# SCH_Controlador-de-Voo_2026-04-27.net
KiCad netlist of a schematic drawn in EasyEDA
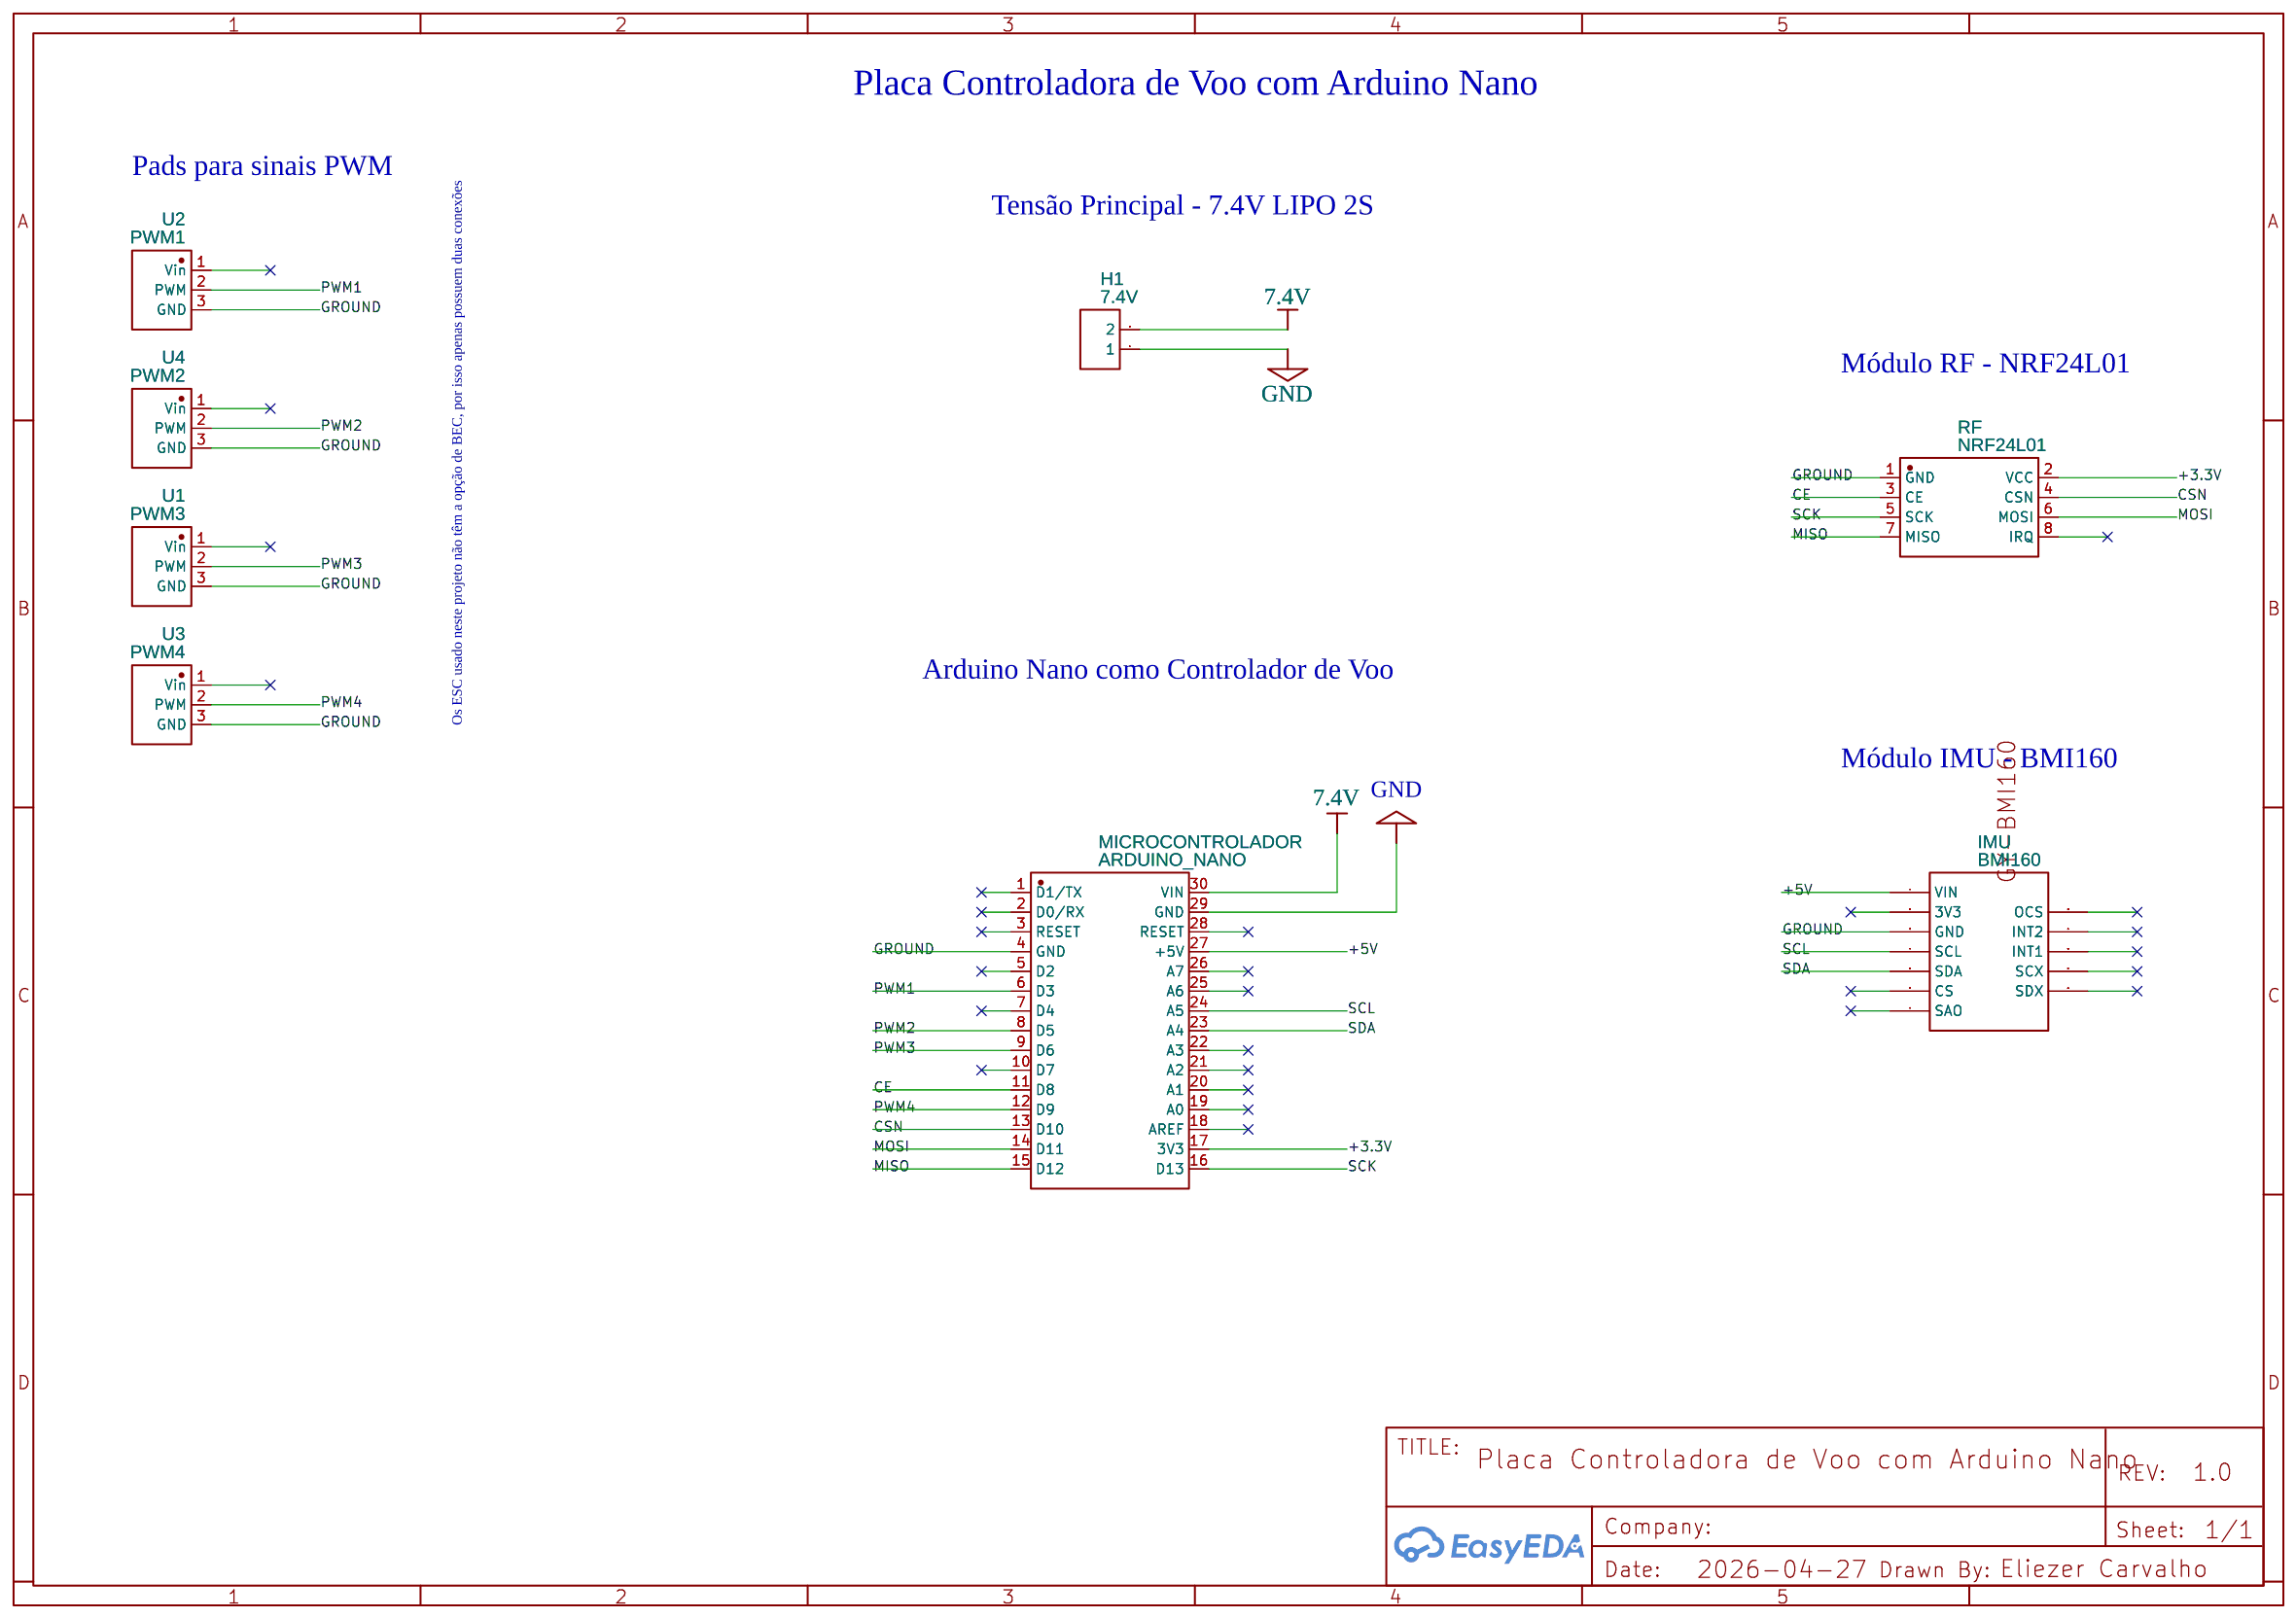
[diagram p0: schematic sheet]

(export (version "E")
  (design (tool "Eeschema 10.0.6"))
  (components
    (comp (ref "H1") (value "7.4V") (libsource (lib "") (part "HDR-F-2.54_1x2")))
    (comp (ref "IMU") (value "BMI160") (libsource (lib "") (part "BMI160 COPY")))
    (comp (ref "MICROCONTROLADOR") (value "ARDUINO_NANO") (libsource (lib "") (part "ARDUINO_NANO")))
    (comp (ref "RF")
      (value "NRF24L01")
      (fields (field (name "Manufacturer Part") "nRF24L01+PA+LNA"))
      (libsource (lib "") (part "NRF24L01+PA+LNA"))
    )
    (comp (ref "U1") (value "PWM3") (libsource (lib "") (part "PWM-Controller")))
    (comp (ref "U2") (value "PWM1") (libsource (lib "") (part "PWM-Controller")))
    (comp (ref "U3") (value "PWM4") (libsource (lib "") (part "PWM-Controller")))
    (comp (ref "U4") (value "PWM2") (libsource (lib "") (part "PWM-Controller")))
  )
  (nets
    (net (code "1") (name "/+3.3V") (class "Default")
      (node (ref "MICROCONTROLADOR") (pin "17") (pinfunction "3V3_17") (pintype "unspecified"))
      (node (ref "RF") (pin "2") (pinfunction "VCC_2") (pintype "unspecified"))
    )
    (net (code "2") (name "/+5V") (class "Default")
      (node (ref "IMU") (pin "7") (pinfunction "VIN_7") (pintype "unspecified"))
      (node (ref "MICROCONTROLADOR") (pin "27") (pinfunction "+5V_27") (pintype "unspecified"))
    )
    (net (code "3") (name "/CE") (class "Default")
      (node (ref "MICROCONTROLADOR") (pin "11") (pinfunction "D8_11") (pintype "unspecified"))
      (node (ref "RF") (pin "3") (pinfunction "CE_3") (pintype "unspecified"))
    )
    (net (code "4") (name "/CSN") (class "Default")
      (node (ref "MICROCONTROLADOR") (pin "13") (pinfunction "D10_13") (pintype "unspecified"))
      (node (ref "RF") (pin "4") (pinfunction "CSN_4") (pintype "unspecified"))
    )
    (net (code "5") (name "/GROUND") (class "Default")
      (node (ref "IMU") (pin "5") (pinfunction "GND_5") (pintype "unspecified"))
      (node (ref "MICROCONTROLADOR") (pin "4") (pinfunction "GND_4") (pintype "unspecified"))
      (node (ref "RF") (pin "1") (pinfunction "GND_1") (pintype "unspecified"))
      (node (ref "U1") (pin "3") (pinfunction "GND_3") (pintype "unspecified"))
      (node (ref "U2") (pin "3") (pinfunction "GND_3") (pintype "unspecified"))
      (node (ref "U3") (pin "3") (pinfunction "GND_3") (pintype "unspecified"))
      (node (ref "U4") (pin "3") (pinfunction "GND_3") (pintype "unspecified"))
    )
    (net (code "6") (name "/MISO") (class "Default")
      (node (ref "MICROCONTROLADOR") (pin "15") (pinfunction "D12_15") (pintype "unspecified"))
      (node (ref "RF") (pin "7") (pinfunction "MISO_7") (pintype "unspecified"))
    )
    (net (code "7") (name "/MOSI") (class "Default")
      (node (ref "MICROCONTROLADOR") (pin "14") (pinfunction "D11_14") (pintype "unspecified"))
      (node (ref "RF") (pin "6") (pinfunction "MOSI_6") (pintype "unspecified"))
    )
    (net (code "8") (name "/PWM1") (class "Default")
      (node (ref "MICROCONTROLADOR") (pin "6") (pinfunction "D3_6") (pintype "unspecified"))
      (node (ref "U2") (pin "2") (pinfunction "PWM_2") (pintype "unspecified"))
    )
    (net (code "9") (name "/PWM2") (class "Default")
      (node (ref "MICROCONTROLADOR") (pin "8") (pinfunction "D5_8") (pintype "unspecified"))
      (node (ref "U4") (pin "2") (pinfunction "PWM_2") (pintype "unspecified"))
    )
    (net (code "10") (name "/PWM3") (class "Default")
      (node (ref "MICROCONTROLADOR") (pin "9") (pinfunction "D6_9") (pintype "unspecified"))
      (node (ref "U1") (pin "2") (pinfunction "PWM_2") (pintype "unspecified"))
    )
    (net (code "11") (name "/PWM4") (class "Default")
      (node (ref "MICROCONTROLADOR") (pin "12") (pinfunction "D9_12") (pintype "unspecified"))
      (node (ref "U3") (pin "2") (pinfunction "PWM_2") (pintype "unspecified"))
    )
    (net (code "12") (name "/SCK") (class "Default")
      (node (ref "MICROCONTROLADOR") (pin "16") (pinfunction "D13_16") (pintype "unspecified"))
      (node (ref "RF") (pin "5") (pinfunction "SCK_5") (pintype "unspecified"))
    )
    (net (code "13") (name "/SCL") (class "Default")
      (node (ref "IMU") (pin "4") (pinfunction "SCL_4") (pintype "unspecified"))
      (node (ref "MICROCONTROLADOR") (pin "24") (pinfunction "A5_24") (pintype "unspecified"))
    )
    (net (code "14") (name "/SDA") (class "Default")
      (node (ref "IMU") (pin "3") (pinfunction "SDA_3") (pintype "unspecified"))
      (node (ref "MICROCONTROLADOR") (pin "23") (pinfunction "A4_23") (pintype "unspecified"))
    )
    (net (code "15") (name "7.4V") (class "Default")
      (node (ref "H1") (pin "2") (pinfunction "2_2") (pintype "input"))
      (node (ref "MICROCONTROLADOR") (pin "30") (pinfunction "VIN_30") (pintype "unspecified"))
    )
    (net (code "16") (name "GND") (class "Default")
      (node (ref "H1") (pin "1") (pinfunction "1_1") (pintype "input"))
      (node (ref "MICROCONTROLADOR") (pin "29") (pinfunction "GND_29") (pintype "unspecified"))
    )
    (net (code "17") (name "unconnected-(IMU-3V3-Pad6)") (class "Default")
      (node (ref "IMU") (pin "6") (pinfunction "3V3_6") (pintype "unspecified+no_connect"))
    )
    (net (code "18") (name "unconnected-(IMU-CS-Pad2)") (class "Default")
      (node (ref "IMU") (pin "2") (pinfunction "CS_2") (pintype "unspecified+no_connect"))
    )
    (net (code "19") (name "unconnected-(IMU-INT1-Pad10)") (class "Default")
      (node (ref "IMU") (pin "10") (pinfunction "INT1_10") (pintype "unspecified+no_connect"))
    )
    (net (code "20") (name "unconnected-(IMU-INT2-Pad9)") (class "Default")
      (node (ref "IMU") (pin "9") (pinfunction "INT2_9") (pintype "unspecified+no_connect"))
    )
    (net (code "21") (name "unconnected-(IMU-OCS-Pad8)") (class "Default")
      (node (ref "IMU") (pin "8") (pinfunction "OCS_8") (pintype "unspecified+no_connect"))
    )
    (net (code "22") (name "unconnected-(IMU-SAO-Pad1)") (class "Default")
      (node (ref "IMU") (pin "1") (pinfunction "SAO_1") (pintype "unspecified+no_connect"))
    )
    (net (code "23") (name "unconnected-(IMU-SCX-Pad11)") (class "Default")
      (node (ref "IMU") (pin "11") (pinfunction "SCX_11") (pintype "unspecified+no_connect"))
    )
    (net (code "24") (name "unconnected-(IMU-SDX-Pad12)") (class "Default")
      (node (ref "IMU") (pin "12") (pinfunction "SDX_12") (pintype "unspecified+no_connect"))
    )
    (net (code "25") (name "unconnected-(MICROCONTROLADOR-A0-Pad19)") (class "Default")
      (node (ref "MICROCONTROLADOR") (pin "19") (pinfunction "A0_19") (pintype "unspecified+no_connect"))
    )
    (net (code "26") (name "unconnected-(MICROCONTROLADOR-A1-Pad20)") (class "Default")
      (node (ref "MICROCONTROLADOR") (pin "20") (pinfunction "A1_20") (pintype "unspecified+no_connect"))
    )
    (net (code "27") (name "unconnected-(MICROCONTROLADOR-A2-Pad21)") (class "Default")
      (node (ref "MICROCONTROLADOR") (pin "21") (pinfunction "A2_21") (pintype "unspecified+no_connect"))
    )
    (net (code "28") (name "unconnected-(MICROCONTROLADOR-A3-Pad22)") (class "Default")
      (node (ref "MICROCONTROLADOR") (pin "22") (pinfunction "A3_22") (pintype "unspecified+no_connect"))
    )
    (net (code "29") (name "unconnected-(MICROCONTROLADOR-A6-Pad25)") (class "Default")
      (node (ref "MICROCONTROLADOR") (pin "25") (pinfunction "A6_25") (pintype "unspecified+no_connect"))
    )
    (net (code "30") (name "unconnected-(MICROCONTROLADOR-A7-Pad26)") (class "Default")
      (node (ref "MICROCONTROLADOR") (pin "26") (pinfunction "A7_26") (pintype "unspecified+no_connect"))
    )
    (net (code "31") (name "unconnected-(MICROCONTROLADOR-AREF-Pad18)") (class "Default")
      (node (ref "MICROCONTROLADOR") (pin "18") (pinfunction "AREF_18") (pintype "unspecified+no_connect"))
    )
    (net (code "32") (name "unconnected-(MICROCONTROLADOR-D0{slash}RX-Pad2)") (class "Default")
      (node (ref "MICROCONTROLADOR") (pin "2") (pinfunction "D0/RX_2") (pintype "unspecified+no_connect"))
    )
    (net (code "33") (name "unconnected-(MICROCONTROLADOR-D1{slash}TX-Pad1)") (class "Default")
      (node (ref "MICROCONTROLADOR") (pin "1") (pinfunction "D1/TX_1") (pintype "unspecified+no_connect"))
    )
    (net (code "34") (name "unconnected-(MICROCONTROLADOR-D2-Pad5)") (class "Default")
      (node (ref "MICROCONTROLADOR") (pin "5") (pinfunction "D2_5") (pintype "unspecified+no_connect"))
    )
    (net (code "35") (name "unconnected-(MICROCONTROLADOR-D4-Pad7)") (class "Default")
      (node (ref "MICROCONTROLADOR") (pin "7") (pinfunction "D4_7") (pintype "unspecified+no_connect"))
    )
    (net (code "36") (name "unconnected-(MICROCONTROLADOR-D7-Pad10)") (class "Default")
      (node (ref "MICROCONTROLADOR") (pin "10") (pinfunction "D7_10") (pintype "unspecified+no_connect"))
    )
    (net (code "37") (name "unconnected-(MICROCONTROLADOR-RESET-Pad3)") (class "Default")
      (node (ref "MICROCONTROLADOR") (pin "3") (pinfunction "RESET_3") (pintype "unspecified+no_connect"))
    )
    (net (code "38") (name "unconnected-(MICROCONTROLADOR-RESET-Pad28)") (class "Default")
      (node (ref "MICROCONTROLADOR") (pin "28") (pinfunction "RESET_28") (pintype "unspecified+no_connect"))
    )
    (net (code "39") (name "unconnected-(RF-IRQ-Pad8)") (class "Default")
      (node (ref "RF") (pin "8") (pinfunction "IRQ_8") (pintype "unspecified+no_connect"))
    )
    (net (code "40") (name "unconnected-(U1-Vin-Pad1)") (class "Default")
      (node (ref "U1") (pin "1") (pinfunction "Vin_1") (pintype "unspecified+no_connect"))
    )
    (net (code "41") (name "unconnected-(U2-Vin-Pad1)") (class "Default")
      (node (ref "U2") (pin "1") (pinfunction "Vin_1") (pintype "unspecified+no_connect"))
    )
    (net (code "42") (name "unconnected-(U3-Vin-Pad1)") (class "Default")
      (node (ref "U3") (pin "1") (pinfunction "Vin_1") (pintype "unspecified+no_connect"))
    )
    (net (code "43") (name "unconnected-(U4-Vin-Pad1)") (class "Default")
      (node (ref "U4") (pin "1") (pinfunction "Vin_1") (pintype "unspecified+no_connect"))
    )
  )
)
